# AC-DC_3_3V_Power_Supply.net
KiCad netlist of a schematic drawn in EAGLE
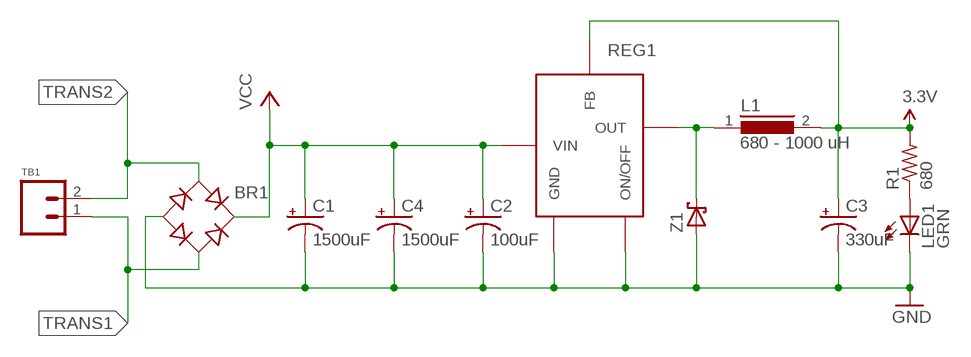
[diagram p0: schematic, sheet 1]

(export (version "E")
  (design (tool "Eeschema 10.0.6"))
  (components
    (comp (ref "BR1")
      (value "BR")
      (footprint "eagle-import:DFS")
      (fields (field (name "MANF") "Comchip Technology"))
      (libsource (lib "eagle-import") (part "BR"))
    )
    (comp (ref "C1")
      (value "1500uF")
      (footprint "eagle-import:J16_CAP")
      (libsource (lib "eagle-import") (part "CAP_POLJ16"))
    )
    (comp (ref "C2")
      (value "100uF")
      (footprint "eagle-import:F_CAP")
      (libsource (lib "eagle-import") (part "CAP_POLF"))
    )
    (comp (ref "C3")
      (value "330uF")
      (footprint "eagle-import:F_CAP")
      (libsource (lib "eagle-import") (part "CAP_POLF"))
    )
    (comp (ref "C4")
      (value "1500uF")
      (footprint "eagle-import:J16_CAP")
      (libsource (lib "eagle-import") (part "CAP_POLJ16"))
    )
    (comp (ref "L1")
      (value "680 - 1000 uH")
      (footprint "eagle-import:DR125")
      (libsource (lib "eagle-import") (part "DR125"))
    )
    (comp (ref "LED1")
      (value "GRN")
      (footprint "eagle-import:0603_LED")
      (fields (field (name "MANF") "Avago Technologies"))
      (libsource (lib "eagle-import") (part "LED0603"))
    )
    (comp (ref "R1")
      (value "680")
      (footprint "eagle-import:0603_RESISTOR")
      (libsource (lib "eagle-import") (part "RESISTOR0603"))
    )
    (comp (ref "REG1")
      (value "TL2575")
      (footprint "eagle-import:TO-263-6")
      (fields (field (name "MANF") "Texas Instruments"))
      (libsource (lib "eagle-import") (part "TL2575"))
    )
    (comp (ref "TB1")
      (value "TERMINAL_BLOCK_2")
      (footprint "eagle-import:TERMINAL_BLOCK_2")
      (fields (field (name "MANF") "Phoenix"))
      (libsource (lib "eagle-import") (part "TERMINAL_BLOCK_2"))
    )
    (comp (ref "Z1")
      (value "SCHOTTKY_DIODE")
      (footprint "eagle-import:SMD_DIODE")
      (fields (field (name "MANF") "Diodes Inc"))
      (libsource (lib "eagle-import") (part "SCHOTTKY_DIODE"))
    )
  )
  (nets
    (net (code "1") (name "3.3V") (class "Default")
      (node (ref "C3") (pin "+") (pinfunction "+_+") (pintype "passive"))
      (node (ref "L1") (pin "2") (pinfunction "2_2") (pintype "passive"))
      (node (ref "R1") (pin "2") (pinfunction "2_2") (pintype "passive"))
      (node (ref "REG1") (pin "4") (pinfunction "FB_4") (pintype "input"))
    )
    (net (code "2") (name "GND") (class "Default")
      (node (ref "BR1") (pin "-") (pinfunction "-_-") (pintype "passive"))
      (node (ref "C1") (pin "-") (pinfunction "-_-") (pintype "passive"))
      (node (ref "C2") (pin "-") (pinfunction "-_-") (pintype "passive"))
      (node (ref "C3") (pin "-") (pinfunction "-_-") (pintype "passive"))
      (node (ref "C4") (pin "-") (pinfunction "-_-") (pintype "passive"))
      (node (ref "LED1") (pin "C") (pinfunction "C_C") (pintype "passive"))
      (node (ref "REG1") (pin "3") (pinfunction "GND_3") (pintype "power_in"))
      (node (ref "REG1") (pin "5") (pinfunction "ON/OFF_5") (pintype "input"))
      (node (ref "Z1") (pin "A") (pinfunction "A_A") (pintype "passive"))
    )
    (net (code "3") (name "Net-(LED1-PadA)") (class "Default")
      (node (ref "LED1") (pin "A") (pinfunction "A_A") (pintype "passive"))
      (node (ref "R1") (pin "1") (pinfunction "1_1") (pintype "passive"))
    )
    (net (code "4") (name "Net-(REG1-OUT)") (class "Default")
      (node (ref "L1") (pin "1") (pinfunction "1_1") (pintype "passive"))
      (node (ref "REG1") (pin "2") (pinfunction "OUT_2") (pintype "power_in"))
      (node (ref "Z1") (pin "C") (pinfunction "C_C") (pintype "passive"))
    )
    (net (code "5") (name "TRANS1") (class "Default")
      (node (ref "BR1") (pin "AC2") (pinfunction "AC2_AC2") (pintype "passive"))
      (node (ref "TB1") (pin "1") (pinfunction "1_1") (pintype "passive"))
    )
    (net (code "6") (name "TRANS2") (class "Default")
      (node (ref "BR1") (pin "AC1") (pinfunction "AC1_AC1") (pintype "passive"))
      (node (ref "TB1") (pin "2") (pinfunction "2_2") (pintype "passive"))
    )
    (net (code "7") (name "VCC") (class "Default")
      (node (ref "BR1") (pin "+") (pinfunction "+_+") (pintype "passive"))
      (node (ref "C1") (pin "+") (pinfunction "+_+") (pintype "passive"))
      (node (ref "C2") (pin "+") (pinfunction "+_+") (pintype "passive"))
      (node (ref "C4") (pin "+") (pinfunction "+_+") (pintype "passive"))
      (node (ref "REG1") (pin "1") (pinfunction "VIN_1") (pintype "power_in"))
    )
  )
)
